# AI_Audio_Module.net
KiCad netlist of a schematic drawn in Altium Designer
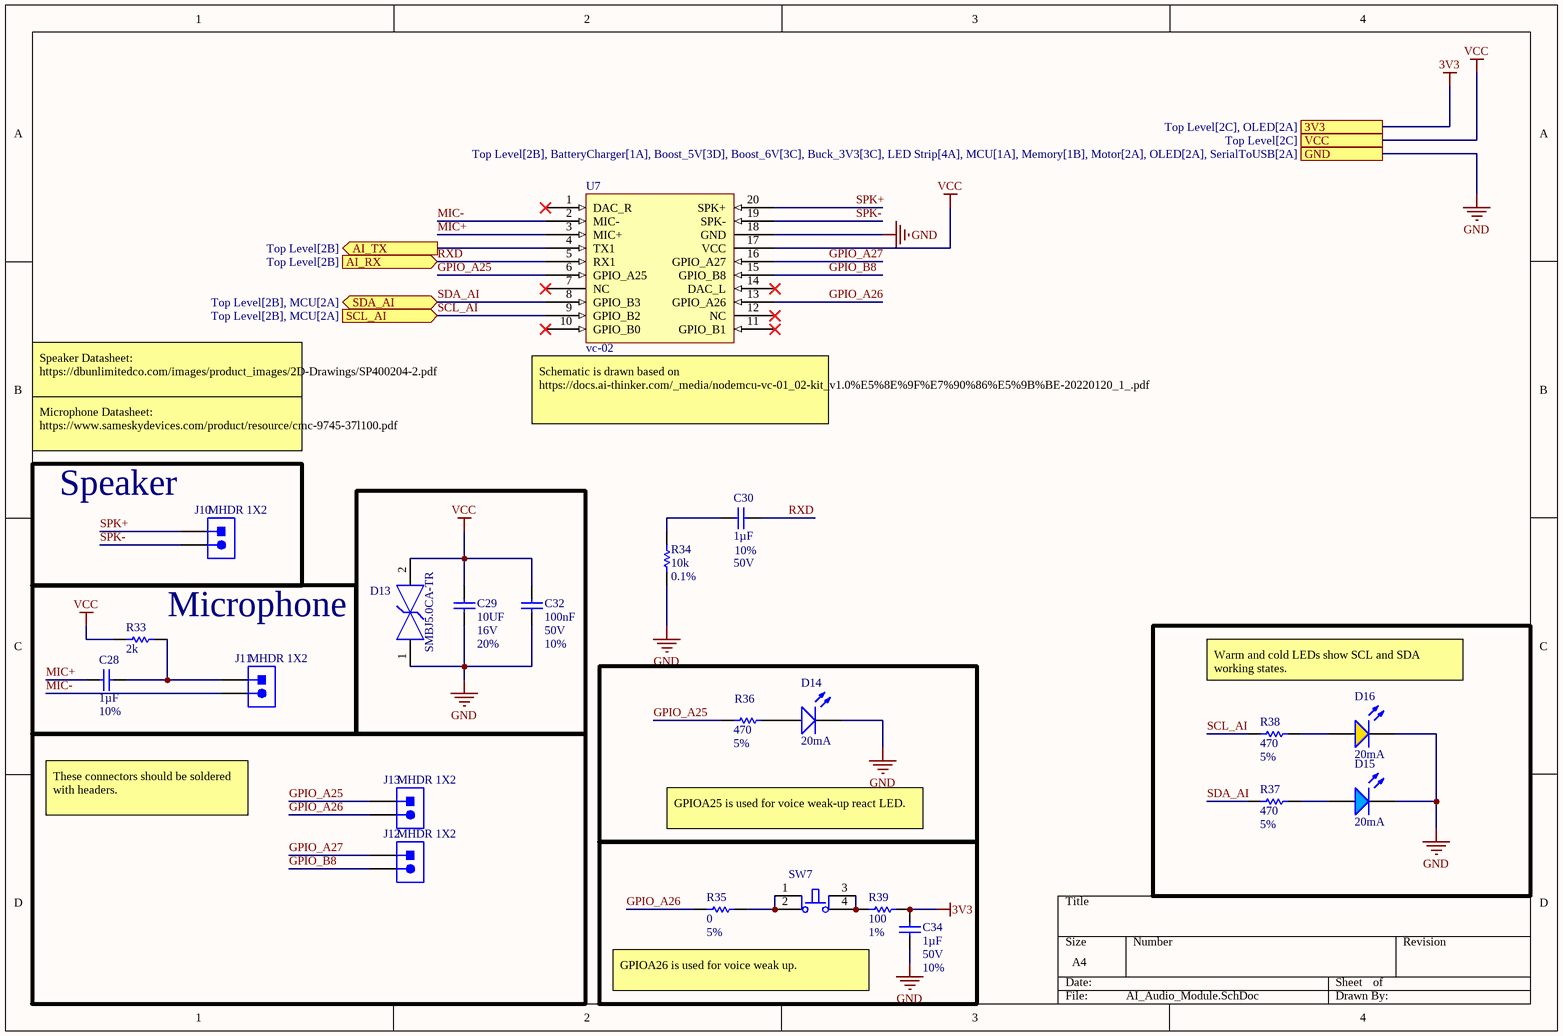
[diagram p0: AI_Audio_Module.SchDoc]

(export (version "E")
  (design (tool "Eeschema 10.0.6"))
  (components
    (comp (ref "C28")
      (value "1µF")
      (footprint "0603_CAP")
      (description "Capacitor Surface Mount 0603 Footprint 1UF 50V 10% Tolerance Ceramic X7R")
      (fields
        (field (name "TOLERANCE") "10%")
        (field (name "VOLTAGE") "50V")
        (field (name "MANUFACTURER") "Various")
      )
      (libsource (lib "University of Pennsylvania (ESE)") (part "cap"))
    )
    (comp (ref "C29")
      (value "10UF")
      (footprint "0603_CAP")
      (description "Capacitor Surface Mount 0603 Footprint 10UF 16V 20% Tolerance Ceramic X5R")
      (fields
        (field (name "MANUFACTURER") "Various")
        (field (name "VOLTAGE") "16V")
        (field (name "TOLERANCE") "20%")
        (field (name "Comment") "CAP 0603 10UF 16V 20% X5R")
      )
      (libsource (lib "University of Pennsylvania (ESE)") (part "cap"))
    )
    (comp (ref "C30")
      (value "1µF")
      (footprint "0603_CAP")
      (description "Capacitor Surface Mount 0603 Footprint 1UF 50V 10% Tolerance Ceramic X7R")
      (fields
        (field (name "TOLERANCE") "10%")
        (field (name "VOLTAGE") "50V")
        (field (name "MANUFACTURER") "Various")
        (field (name "Comment") "CAP 0603 1UF 50V 10% X7R")
      )
      (libsource (lib "University of Pennsylvania (ESE)") (part "cap"))
    )
    (comp (ref "C32")
      (value "100nF")
      (footprint "0603_CAP")
      (description "Capacitor Surface Mount 0603 Footprint 0.1UF 50V 10% Tolerance Ceramic X7R 100nF")
      (fields
        (field (name "VOLTAGE") "50V")
        (field (name "TOLERANCE") "10%")
        (field (name "MANUFACTURER") "Various")
        (field (name "JLCPCB PART #") "C14663")
      )
      (libsource (lib "University of Pennsylvania (ESE)") (part "cap"))
    )
    (comp (ref "C34")
      (value "1µF")
      (footprint "0603_CAP")
      (description "Capacitor Surface Mount 0603 Footprint 1UF 50V 10% Tolerance Ceramic X7R")
      (fields
        (field (name "VOLTAGE") "50V")
        (field (name "MANUFACTURER") "Various")
        (field (name "TOLERANCE") "10%")
        (field (name "Comment") "CAP 0603 1UF 50V 10% X7R")
      )
      (libsource (lib "University of Pennsylvania (ESE)") (part "cap"))
    )
    (comp (ref "D13")
      (value "SMBJ5.0CA-TR")
      (footprint "FP-SMB-CA-MFG")
      (description "TVS DIODE 5V 13.4V SMB")
      (fields
        (field (name "MANUFACTURER") "STMicroelectronics")
        (field (name "OCTOPART") "https://octopart.com/smbj5.0ca-tr-stmicroelectronics-347080")
      )
      (libsource (lib "Altium Content Vault") (part "876f4347bf90aa6f500f43e3cd03972"))
    )
    (comp (ref "D14")
      (value "LSM0805543V")
      (footprint "LED_0805_WHITE")
      (description "LED Uni-Color Blue 469nm Automotive 2-Pin Chip 0805(2012Metric) T/R")
      (fields (field (name "CURRENT") "20mA"))
      (libsource (lib "University of Pennsylvania (ESE)") (part "LED-WHITE-AK-2"))
    )
    (comp (ref "D15")
      (value "LSM0805463V")
      (footprint "LED_0805_BLUE")
      (description "LED Uni-Color Blue 469nm Automotive 2-Pin Chip 0805(2012Metric) T/R")
      (fields (field (name "CURRENT") "20mA"))
      (libsource (lib "University of Pennsylvania (ESE)") (part "LED-BLUE-AK-2"))
    )
    (comp (ref "D16")
      (value "LSM0805472V")
      (footprint "LED_0805_YELLOW")
      (description "LED Uni-Color Yellow 590nm Automotive 2-Pin Chip 0805(2012Metric) T/R")
      (fields (field (name "CURRENT") "20mA"))
      (libsource (lib "University of Pennsylvania (ESE)") (part "LED-YELLOW-AK-2"))
    )
    (comp (ref "J10")
      (value "MHDR 1X2")
      (footprint "PH1-02-UA")
      (description "Header, 2-Pin, 0.1in Pitch, Male")
      (libsource (lib "University of Pennsylvania (ESE)") (part "Header 1X2"))
    )
    (comp (ref "J11")
      (value "MHDR 1X2")
      (footprint "PH1-02-UA")
      (description "Header, 2-Pin, 0.1in Pitch, Male")
      (libsource (lib "University of Pennsylvania (ESE)") (part "Header 1X2"))
    )
    (comp (ref "J12")
      (value "MHDR 1X2")
      (footprint "PH1-02-UA")
      (description "Header, 2-Pin, 0.1in Pitch, Male")
      (libsource (lib "University of Pennsylvania (ESE)") (part "Header 1X2"))
    )
    (comp (ref "J13")
      (value "MHDR 1X2")
      (footprint "PH1-02-UA")
      (description "Header, 2-Pin, 0.1in Pitch, Male")
      (libsource (lib "University of Pennsylvania (ESE)") (part "Header 1X2"))
    )
    (comp (ref "R33")
      (value "2k")
      (footprint "0603_RES")
      (description "Resistor Surface Mount, 2K Ohms, 0603 Footprint, 0.1% Tolerance 0.1W")
      (fields (field (name "MANUFACTURER") "Various") (field (name "TOLERANCE") "0.1%"))
      (libsource (lib "University of Pennsylvania (ESE)") (part "res"))
    )
    (comp (ref "R34")
      (value "10k")
      (footprint "0603_RES")
      (description "Resistor Surface Mount, 10K Ohms, 0603 Footprint, 0.1% Tolerance 0.1W")
      (fields
        (field (name "TOLERANCE") "0.1%")
        (field (name "MANUFACTURER") "Various")
        (field (name "Comment") "RES 0603 10K 0.1%")
      )
      (libsource (lib "University of Pennsylvania (ESE)") (part "res"))
    )
    (comp (ref "R35")
      (value "0")
      (footprint "0603_RES")
      (description "Resistor Surface Mount, 0 Ohms, 0603 Footprint, 5% Tolerance 0.1W")
      (fields
        (field (name "JLCPCB PART #") "C21189")
        (field (name "TOLERANCE") "5%")
        (field (name "MANUFACTURER") "Various")
      )
      (libsource (lib "University of Pennsylvania (ESE)") (part "res"))
    )
    (comp (ref "R36")
      (value "470")
      (footprint "0805_RES")
      (description "Resistor Surface Mount, 470 Ohms, 0805 Footprint, 5% Tolerance 0.125W")
      (fields
        (field (name "TOLERANCE") "5%")
        (field (name "MANUFACTURER") "Various")
        (field (name "Comment") "RES 0805 470 5%")
      )
      (libsource (lib "University of Pennsylvania (ESE)") (part "res"))
    )
    (comp (ref "R37")
      (value "470")
      (footprint "0805_RES")
      (description "Resistor Surface Mount, 470 Ohms, 0805 Footprint, 5% Tolerance 0.125W")
      (fields
        (field (name "TOLERANCE") "5%")
        (field (name "MANUFACTURER") "Various")
        (field (name "Comment") "RES 0805 470 5%")
      )
      (libsource (lib "University of Pennsylvania (ESE)") (part "res"))
    )
    (comp (ref "R38")
      (value "470")
      (footprint "0805_RES")
      (description "Resistor Surface Mount, 470 Ohms, 0805 Footprint, 5% Tolerance 0.125W")
      (fields
        (field (name "TOLERANCE") "5%")
        (field (name "MANUFACTURER") "Various")
        (field (name "Comment") "RES 0805 470 5%")
      )
      (libsource (lib "University of Pennsylvania (ESE)") (part "res"))
    )
    (comp (ref "R39")
      (value "100")
      (footprint "0603_RES")
      (description "Resistor Surface Mount, 100 Ohms, 0603 Footprint, 1% Tolerance 0.1W")
      (fields
        (field (name "TOLERANCE") "1%")
        (field (name "MANUFACTURER") "Various")
        (field (name "Comment") "RES 0603 100 1%")
      )
      (libsource (lib "University of Pennsylvania (ESE)") (part "res"))
    )
    (comp (ref "SW7")
      (value "PTS810SJK250SMTRLFS")
      (footprint "PTS810SJK250SMTRLFS-Footprint-1")
      (libsource (lib "University of Pennsylvania (ESE)") (part "Tactile Switch 4 Pin"))
    )
    (comp (ref "U7")
      (value "vc-02")
      (footprint "SON180P1700X265-20N")
      (description "AI Audio Module")
      (libsource (lib "University of Pennsylvania (ESE)") (part "VC-02"))
    )
  )
  (nets
    (net (code "1") (name "/AI_TX") (class "Default")
      (node (ref "U7") (pin "4") (pinfunction "TX1_4") (pintype "input"))
    )
    (net (code "2") (name "/GPIO_A25") (class "Default")
      (node (ref "J13") (pin "1") (pinfunction "1_1") (pintype "passive"))
      (node (ref "R36") (pin "1") (pinfunction "1_1") (pintype "passive"))
      (node (ref "U7") (pin "6") (pinfunction "GPIO_A25_6") (pintype "input"))
    )
    (net (code "3") (name "/GPIO_A26") (class "Default")
      (node (ref "J13") (pin "2") (pinfunction "2_2") (pintype "passive"))
      (node (ref "R35") (pin "1") (pinfunction "1_1") (pintype "passive"))
      (node (ref "U7") (pin "13") (pinfunction "GPIO_A26_13") (pintype "input"))
    )
    (net (code "4") (name "/GPIO_A27") (class "Default")
      (node (ref "J12") (pin "1") (pinfunction "1_1") (pintype "passive"))
      (node (ref "U7") (pin "16") (pinfunction "GPIO_A27_16") (pintype "input"))
    )
    (net (code "5") (name "/GPIO_B8") (class "Default")
      (node (ref "J12") (pin "2") (pinfunction "2_2") (pintype "passive"))
      (node (ref "U7") (pin "15") (pinfunction "GPIO_B8_15") (pintype "input"))
    )
    (net (code "6") (name "/MIC+") (class "Default")
      (node (ref "C28") (pin "1") (pinfunction "1_1") (pintype "passive"))
      (node (ref "U7") (pin "3") (pinfunction "MIC+_3") (pintype "input"))
    )
    (net (code "7") (name "/MIC-") (class "Default")
      (node (ref "J11") (pin "2") (pinfunction "2_2") (pintype "passive"))
      (node (ref "U7") (pin "2") (pinfunction "MIC-_2") (pintype "input"))
    )
    (net (code "8") (name "/RXD") (class "Default")
      (node (ref "C30") (pin "2") (pinfunction "2_2") (pintype "passive"))
      (node (ref "U7") (pin "5") (pinfunction "RX1_5") (pintype "input"))
    )
    (net (code "9") (name "/SCL_AI") (class "Default")
      (node (ref "R38") (pin "1") (pinfunction "1_1") (pintype "passive"))
      (node (ref "U7") (pin "9") (pinfunction "GPIO_B2_9") (pintype "input"))
    )
    (net (code "10") (name "/SDA_AI") (class "Default")
      (node (ref "R37") (pin "1") (pinfunction "1_1") (pintype "passive"))
      (node (ref "U7") (pin "8") (pinfunction "GPIO_B3_8") (pintype "input"))
    )
    (net (code "11") (name "/SPK+") (class "Default")
      (node (ref "J10") (pin "1") (pinfunction "1_1") (pintype "passive"))
      (node (ref "U7") (pin "20") (pinfunction "SPK+_20") (pintype "input"))
    )
    (net (code "12") (name "/SPK-") (class "Default")
      (node (ref "J10") (pin "2") (pinfunction "2_2") (pintype "passive"))
      (node (ref "U7") (pin "19") (pinfunction "SPK-_19") (pintype "input"))
    )
    (net (code "13") (name "3V3") (class "Default")
      (node (ref "C34") (pin "2") (pinfunction "2_2") (pintype "passive"))
      (node (ref "R39") (pin "2") (pinfunction "2_2") (pintype "passive"))
    )
    (net (code "14") (name "GND") (class "Default")
      (node (ref "C29") (pin "1") (pinfunction "1_1") (pintype "passive"))
      (node (ref "C32") (pin "1") (pinfunction "1_1") (pintype "passive"))
      (node (ref "C34") (pin "1") (pinfunction "1_1") (pintype "passive"))
      (node (ref "D13") (pin "1") (pinfunction "1_1") (pintype "passive"))
      (node (ref "D14") (pin "K") (pinfunction "K_K") (pintype "passive"))
      (node (ref "D15") (pin "K") (pinfunction "K_K") (pintype "passive"))
      (node (ref "D16") (pin "K") (pinfunction "K_K") (pintype "passive"))
      (node (ref "R34") (pin "1") (pinfunction "1_1") (pintype "passive"))
      (node (ref "U7") (pin "18") (pinfunction "GND_18") (pintype "power_in"))
    )
    (net (code "15") (name "Net-(C28-Pad2)") (class "Default")
      (node (ref "C28") (pin "2") (pinfunction "2_2") (pintype "passive"))
      (node (ref "J11") (pin "1") (pinfunction "1_1") (pintype "passive"))
      (node (ref "R33") (pin "2") (pinfunction "2_2") (pintype "passive"))
    )
    (net (code "16") (name "Net-(C30-Pad1)") (class "Default")
      (node (ref "C30") (pin "1") (pinfunction "1_1") (pintype "passive"))
      (node (ref "R34") (pin "2") (pinfunction "2_2") (pintype "passive"))
    )
    (net (code "17") (name "Net-(D14-PadA)") (class "Default")
      (node (ref "D14") (pin "A") (pinfunction "A_A") (pintype "passive"))
      (node (ref "R36") (pin "2") (pinfunction "2_2") (pintype "passive"))
    )
    (net (code "18") (name "Net-(D15-PadA)") (class "Default")
      (node (ref "D15") (pin "A") (pinfunction "A_A") (pintype "passive"))
      (node (ref "R37") (pin "2") (pinfunction "2_2") (pintype "passive"))
    )
    (net (code "19") (name "Net-(D16-PadA)") (class "Default")
      (node (ref "D16") (pin "A") (pinfunction "A_A") (pintype "passive"))
      (node (ref "R38") (pin "2") (pinfunction "2_2") (pintype "passive"))
    )
    (net (code "20") (name "Net-(R35-Pad2)") (class "Default")
      (node (ref "R35") (pin "2") (pinfunction "2_2") (pintype "passive"))
      (node (ref "SW7") (pin "1") (pinfunction "1_1") (pintype "passive"))
      (node (ref "SW7") (pin "2") (pinfunction "2_2") (pintype "passive"))
    )
    (net (code "21") (name "Net-(R39-Pad1)") (class "Default")
      (node (ref "R39") (pin "1") (pinfunction "1_1") (pintype "passive"))
      (node (ref "SW7") (pin "3") (pinfunction "2_3") (pintype "passive"))
      (node (ref "SW7") (pin "4") (pinfunction "4_4") (pintype "passive"))
    )
    (net (code "22") (name "VCC") (class "Default")
      (node (ref "C29") (pin "2") (pinfunction "2_2") (pintype "passive"))
      (node (ref "C32") (pin "2") (pinfunction "2_2") (pintype "passive"))
      (node (ref "D13") (pin "2") (pinfunction "2_2") (pintype "passive"))
      (node (ref "R33") (pin "1") (pinfunction "1_1") (pintype "passive"))
      (node (ref "U7") (pin "17") (pinfunction "VCC_17") (pintype "power_in"))
    )
    (net (code "23") (name "unconnected-(U7-DAC_L-Pad14)") (class "Default")
      (node (ref "U7") (pin "14") (pinfunction "DAC_L_14") (pintype "input+no_connect"))
    )
    (net (code "24") (name "unconnected-(U7-DAC_R-Pad1)") (class "Default")
      (node (ref "U7") (pin "1") (pinfunction "DAC_R_1") (pintype "input+no_connect"))
    )
    (net (code "25") (name "unconnected-(U7-GPIO_B0-Pad10)") (class "Default")
      (node (ref "U7") (pin "10") (pinfunction "GPIO_B0_10") (pintype "input+no_connect"))
    )
    (net (code "26") (name "unconnected-(U7-GPIO_B1-Pad11)") (class "Default")
      (node (ref "U7") (pin "11") (pinfunction "GPIO_B1_11") (pintype "input+no_connect"))
    )
    (net (code "27") (name "unconnected-(U7-NC-Pad7)") (class "Default")
      (node (ref "U7") (pin "7") (pinfunction "NC_7") (pintype "tri_state+no_connect"))
    )
    (net (code "28") (name "unconnected-(U7-NC-Pad12)") (class "Default")
      (node (ref "U7") (pin "12") (pinfunction "NC_12") (pintype "tri_state+no_connect"))
    )
  )
)
